# RobotComputerVision_1_1.net
KiCad netlist of a schematic drawn in Altium Designer
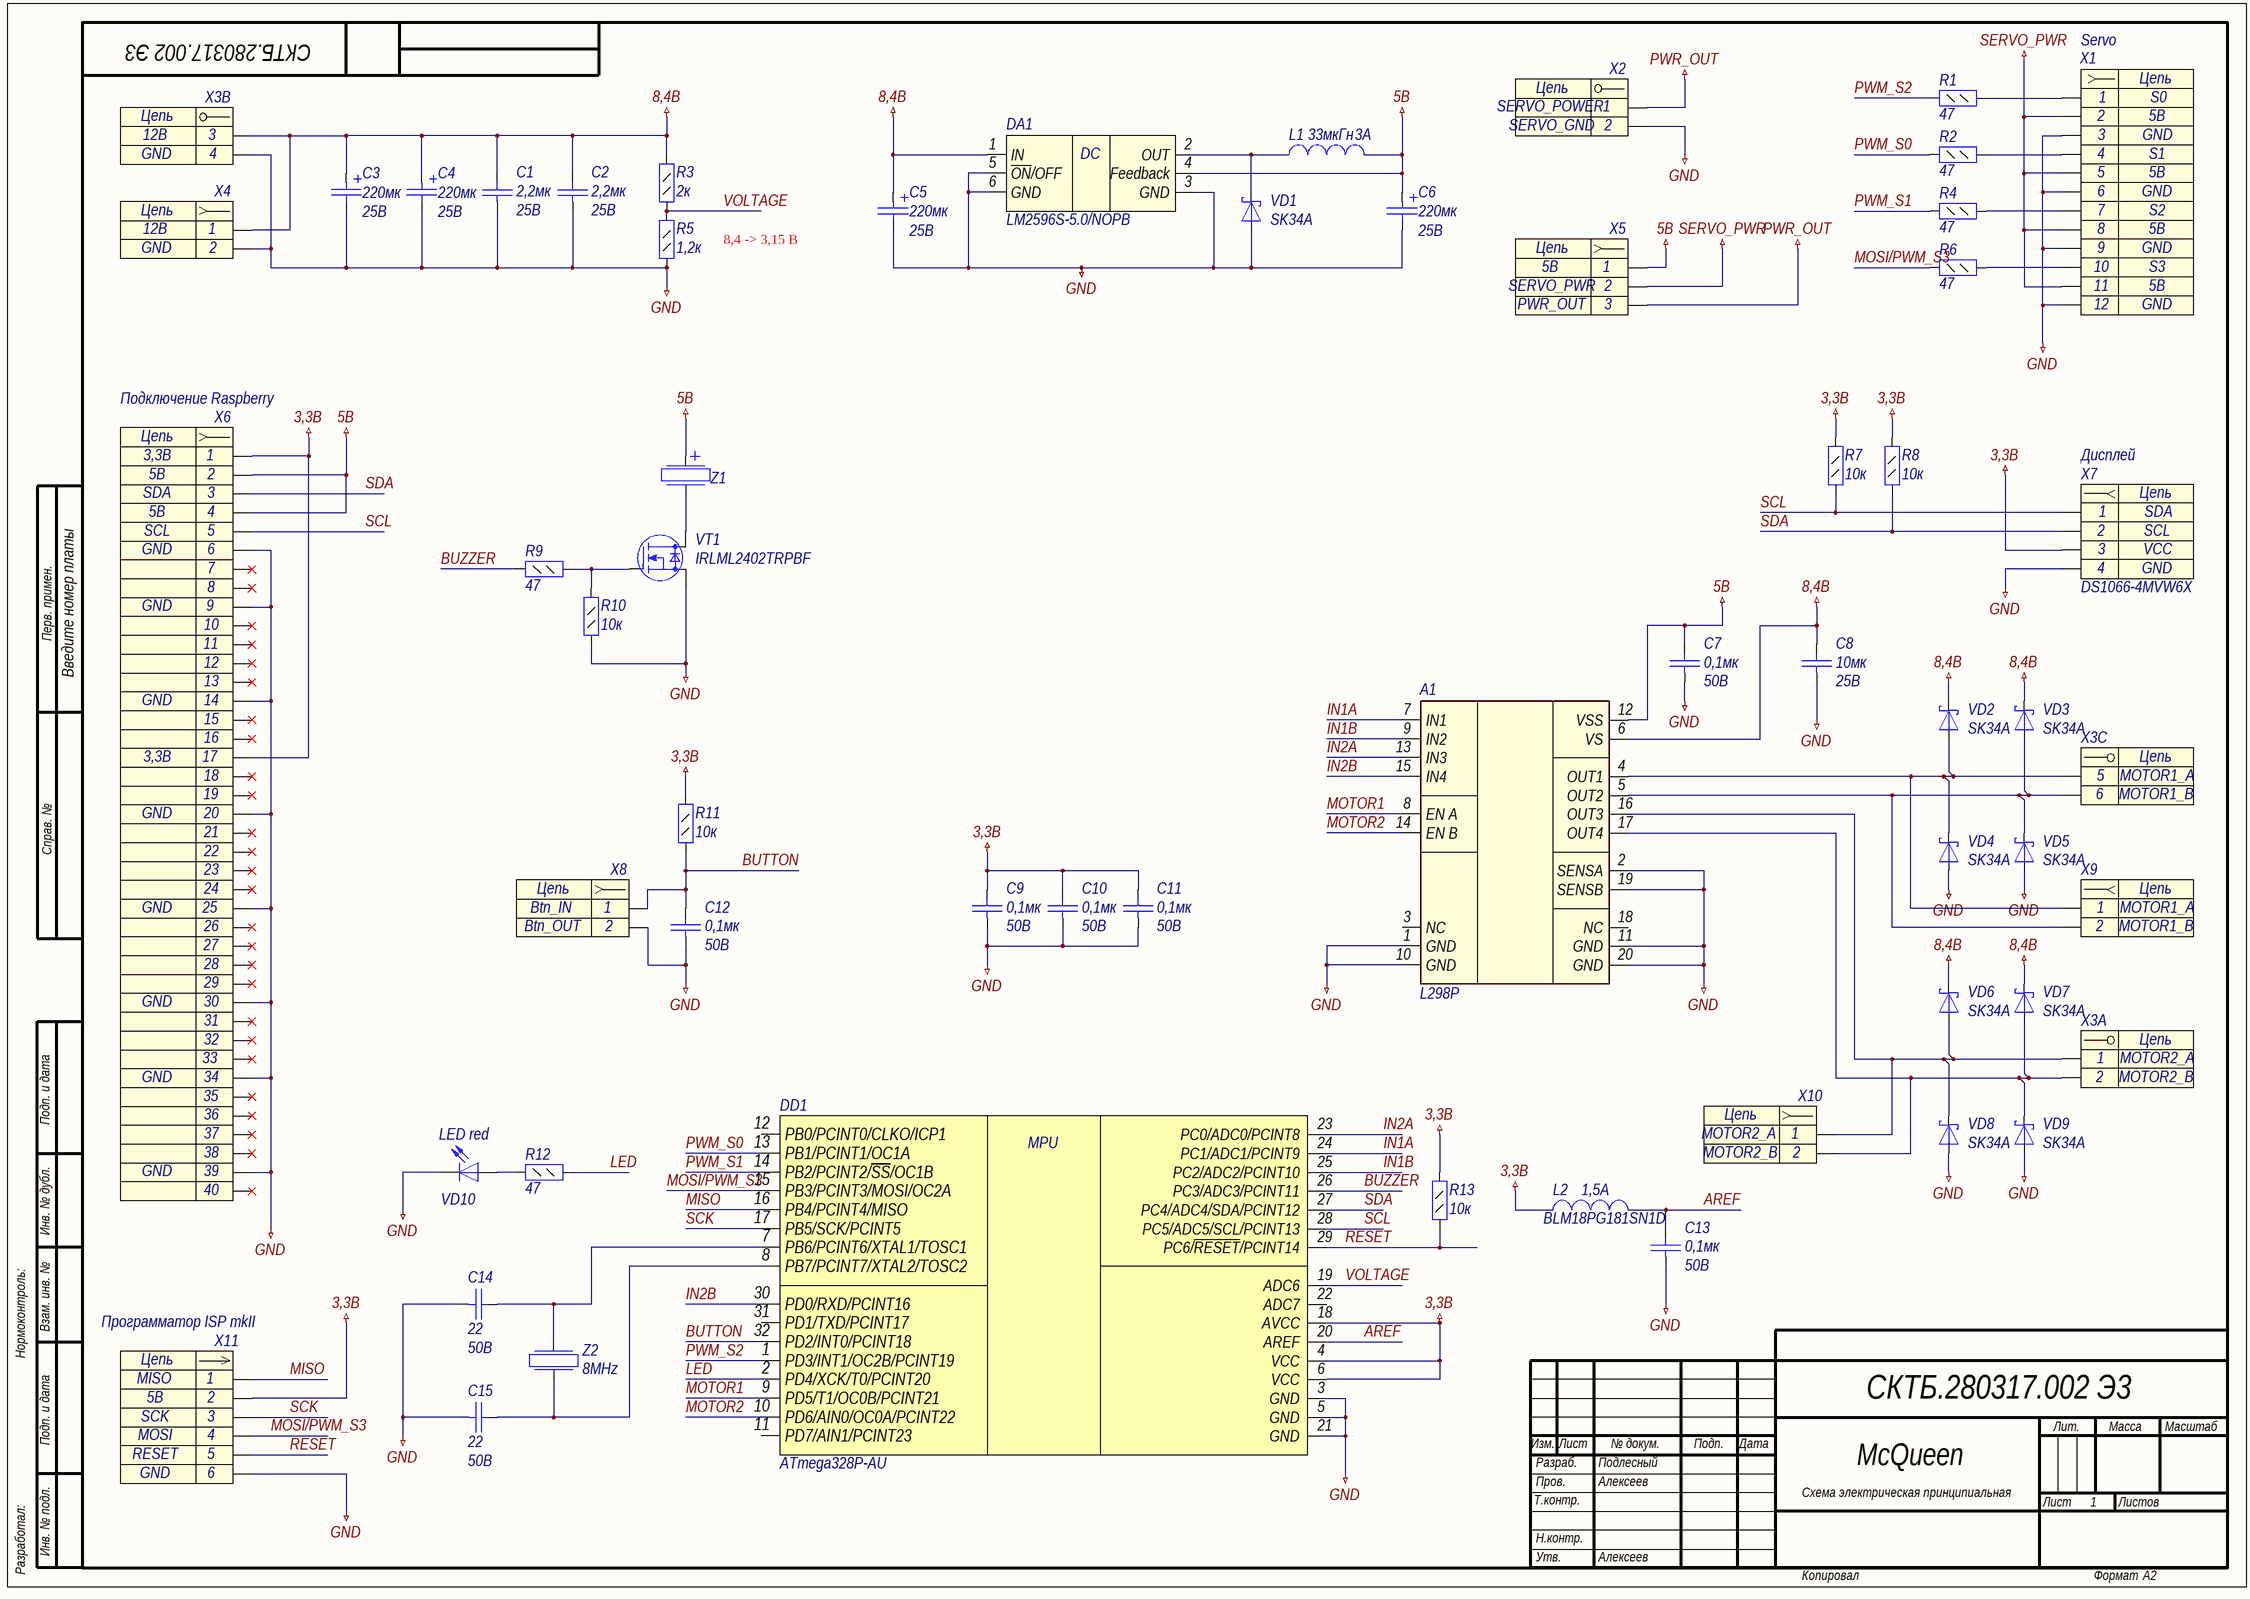
[diagram p0: RobotComputerVision_1.1.SchDoc]

(export (version "E")
  (design (tool "Eeschema 10.0.6"))
  (components
    (comp (ref "A1")
      (value "L298P")
      (footprint "POWERSO20")
      (description "FULL BRIDGE DC MOTOR DRIVER")
      (libsource (lib "MOP44") (part "L298P"))
    )
    (comp (ref "C1")
      (value "2,2мк")
      (footprint "C0805")
      (description "Конденсатор")
      (fields (field (name "VOLTAGE") "25B") (field (name "PART NUMBER") "GRM21BR71E225K"))
      (libsource (lib "MOP44") (part "Capacitor"))
    )
    (comp (ref "C2")
      (value "2,2мк")
      (footprint "C0805")
      (description "Конденсатор")
      (fields (field (name "VOLTAGE") "25B") (field (name "PART NUMBER") "GRM21BR71E225K"))
      (libsource (lib "MOP44") (part "Capacitor"))
    )
    (comp (ref "C3")
      (value "220мк")
      (footprint "Cap_SMD_radial_polar(8x10.2)")
      (description "Конденсатор полярный")
      (fields
        (field (name "VOLTAGE") "25В")
        (field (name "PART NUMBER") "JCK1E221M080105")
        (field (name "Comment") "Capacitor_pol")
      )
      (libsource (lib "MOP44") (part "Capacitor_pol"))
    )
    (comp (ref "C4")
      (value "220мк")
      (footprint "Cap_SMD_radial_polar(8x10.2)")
      (description "Конденсатор полярный")
      (fields
        (field (name "VOLTAGE") "25В")
        (field (name "PART NUMBER") "JCK1E221M080105")
        (field (name "Comment") "Capacitor_pol")
      )
      (libsource (lib "MOP44") (part "Capacitor_pol"))
    )
    (comp (ref "C5")
      (value "220мк")
      (footprint "Cap_SMD_radial_polar(8x10.2)")
      (description "Конденсатор полярный")
      (fields
        (field (name "VOLTAGE") "25В")
        (field (name "PART NUMBER") "JCK1E221M080105")
        (field (name "Comment") "Capacitor_pol")
      )
      (libsource (lib "MOP44") (part "Capacitor_pol"))
    )
    (comp (ref "C6")
      (value "220мк")
      (footprint "Cap_SMD_radial_polar(8x10.2)")
      (description "Конденсатор полярный")
      (fields
        (field (name "VOLTAGE") "25В")
        (field (name "PART NUMBER") "JCK1E221M080105")
        (field (name "Comment") "Capacitor_pol")
      )
      (libsource (lib "MOP44") (part "Capacitor_pol"))
    )
    (comp (ref "C7")
      (value "0,1мк")
      (footprint "C0805")
      (description "Конденсатор")
      (fields (field (name "VOLTAGE") "50В") (field (name "PART NUMBER") "GRM21BR71H104KA01L "))
      (libsource (lib "MOP44") (part "Capacitor"))
    )
    (comp (ref "C8")
      (value "10мк")
      (footprint "C1210")
      (description "Конденсатор")
      (fields (field (name "VOLTAGE") "25В") (field (name "PART NUMBER") "GRM32ER61A106K"))
      (libsource (lib "MOP44") (part "Capacitor"))
    )
    (comp (ref "C9")
      (value "0,1мк")
      (footprint "C0805")
      (description "Конденсатор")
      (fields (field (name "VOLTAGE") "50В") (field (name "PART NUMBER") "GRM21BR71H104KA01L "))
      (libsource (lib "MOP44") (part "Capacitor"))
    )
    (comp (ref "C10")
      (value "0,1мк")
      (footprint "C0805")
      (description "Конденсатор")
      (fields (field (name "VOLTAGE") "50В") (field (name "PART NUMBER") "GRM21BR71H104KA01L "))
      (libsource (lib "MOP44") (part "Capacitor"))
    )
    (comp (ref "C11")
      (value "0,1мк")
      (footprint "C0805")
      (description "Конденсатор")
      (fields (field (name "VOLTAGE") "50В") (field (name "PART NUMBER") "GRM21BR71H104KA01L "))
      (libsource (lib "MOP44") (part "Capacitor"))
    )
    (comp (ref "C12")
      (value "0,1мк")
      (footprint "C0805")
      (description "Конденсатор")
      (fields (field (name "VOLTAGE") "50В") (field (name "PART NUMBER") "GRM21BR71H104KA01L "))
      (libsource (lib "MOP44") (part "Capacitor"))
    )
    (comp (ref "C13")
      (value "0,1мк")
      (footprint "C0805")
      (description "Конденсатор")
      (fields (field (name "VOLTAGE") "50В") (field (name "PART NUMBER") "GRM21BR71H104KA01L "))
      (libsource (lib "MOP44") (part "Capacitor"))
    )
    (comp (ref "C14")
      (value "22")
      (footprint "C0805")
      (description "Конденсатор")
      (fields (field (name "VOLTAGE") "50В") (field (name "PART NUMBER") "MLCC22pFNPO50V5%0805"))
      (libsource (lib "MOP44") (part "Capacitor"))
    )
    (comp (ref "C15")
      (value "22")
      (footprint "C0805")
      (description "Конденсатор")
      (fields (field (name "VOLTAGE") "50В") (field (name "PART NUMBER") "MLCC22pFNPO50V5%0805"))
      (libsource (lib "MOP44") (part "Capacitor"))
    )
    (comp (ref "DA1")
      (value "LM2596S")
      (footprint "TO-263-5")
      (description "3-A Step-Down Voltage Regulator")
      (fields
        (field (name "PART NUMBER") "LM2596S-5.0/NOPB")
        (field (name "MANUFACTURER") "Texas Instruments")
      )
      (libsource (lib "MOP44") (part "LM2596S"))
    )
    (comp (ref "DD1")
      (value "ATmega328P-AU")
      (footprint "TQFP-32")
      (description "Микроконтроллер 8-Бит, picoPower, AVR, 20МГц, 32КБ Flash")
      (libsource (lib "MOP44") (part "ATmega328P-AU"))
    )
    (comp (ref "L1")
      (value "33мкГн")
      (footprint "IND_12.5x12.5")
      (description "EMI Suppression Filter")
      (fields
        (field (name "RATED CURRENT") "3A")
        (field (name "PART NUMBER") "B82477G4333M000")
        (field (name "Comment") "Inductor")
      )
      (libsource (lib "MOP44") (part "Inductor"))
    )
    (comp (ref "L2")
      (value "Inductor")
      (footprint "L0603")
      (description "EMI Suppression Filter")
      (fields (field (name "RATED CURRENT") "1,5A") (field (name "PART NUMBER") "BLM18PG181SN1D"))
      (libsource (lib "MOP44") (part "Inductor"))
    )
    (comp (ref "R1")
      (value "47")
      (footprint "R0805")
      (description "Резистор")
      (fields (field (name "PART NUMBER") "RC0805FR-0747RL") (field (name "POWER") "0,125Вт"))
      (libsource (lib "") (part "Resistor_0,125Вт_1"))
    )
    (comp (ref "R2")
      (value "47")
      (footprint "R0805")
      (description "Резистор")
      (fields (field (name "PART NUMBER") "RC0805FR-0747RL") (field (name "POWER") "0,125Вт"))
      (libsource (lib "") (part "Resistor_0,125Вт_1"))
    )
    (comp (ref "R3")
      (value "2к")
      (footprint "R0805")
      (description "Резистор")
      (fields (field (name "PART NUMBER") "RC0805FR-072KL") (field (name "POWER") "0,125Вт"))
      (libsource (lib "MOP44") (part "Resistor_0,125Вт"))
    )
    (comp (ref "R4")
      (value "47")
      (footprint "R0805")
      (description "Резистор")
      (fields (field (name "PART NUMBER") "RC0805FR-0747RL") (field (name "POWER") "0,125Вт"))
      (libsource (lib "") (part "Resistor_0,125Вт_1"))
    )
    (comp (ref "R5")
      (value "1,2к")
      (footprint "R0805")
      (description "Резистор")
      (fields (field (name "PART NUMBER") "RC0805FR-071K2") (field (name "POWER") "0,125Вт"))
      (libsource (lib "MOP44") (part "Resistor_0,125Вт"))
    )
    (comp (ref "R6")
      (value "47")
      (footprint "R0805")
      (description "Резистор")
      (fields (field (name "PART NUMBER") "RC0805FR-0747RL") (field (name "POWER") "0,125Вт"))
      (libsource (lib "") (part "Resistor_0,125Вт_1"))
    )
    (comp (ref "R7")
      (value "10к")
      (footprint "R0805")
      (description "Резистор")
      (fields (field (name "PART NUMBER") "RC0805FR-0710KL") (field (name "POWER") "0,125Вт"))
      (libsource (lib "MOP44") (part "Resistor_0,125Вт"))
    )
    (comp (ref "R8")
      (value "10к")
      (footprint "R0805")
      (description "Резистор")
      (fields (field (name "PART NUMBER") "RC0805FR-0710KL") (field (name "POWER") "0,125Вт"))
      (libsource (lib "MOP44") (part "Resistor_0,125Вт"))
    )
    (comp (ref "R9")
      (value "47")
      (footprint "R0805")
      (description "Резистор")
      (fields (field (name "PART NUMBER") "RC0805FR-0747RL") (field (name "POWER") "0,125Вт"))
      (libsource (lib "") (part "Resistor_0,125Вт_1"))
    )
    (comp (ref "R10")
      (value "10к")
      (footprint "R0805")
      (description "Резистор")
      (fields (field (name "PART NUMBER") "RC0805FR-0710KL") (field (name "POWER") "0,125Вт"))
      (libsource (lib "MOP44") (part "Resistor_0,125Вт"))
    )
    (comp (ref "R11")
      (value "10к")
      (footprint "R0805")
      (description "Резистор")
      (fields (field (name "PART NUMBER") "RC0805FR-0710KL") (field (name "POWER") "0,125Вт"))
      (libsource (lib "MOP44") (part "Resistor_0,125Вт"))
    )
    (comp (ref "R12")
      (value "47")
      (footprint "R0805")
      (description "Резистор")
      (fields (field (name "PART NUMBER") "RC0805FR-0747RL") (field (name "POWER") "0,125Вт"))
      (libsource (lib "") (part "Resistor_0,125Вт_1"))
    )
    (comp (ref "R13")
      (value "10к")
      (footprint "R0805")
      (description "Резистор")
      (fields (field (name "PART NUMBER") "RC0805FR-0710KL") (field (name "POWER") "0,125Вт"))
      (libsource (lib "MOP44") (part "Resistor_0,125Вт"))
    )
    (comp (ref "VD1")
      (value "DiodeSchottky")
      (footprint "SMA")
      (description "Диод Шоттки")
      (fields (field (name "PART NUMBER") "SK34A"))
      (libsource (lib "MOP44") (part "DiodeSchottky"))
    )
    (comp (ref "VD2")
      (value "DiodeSchottky")
      (footprint "SMA")
      (description "Диод Шоттки")
      (fields (field (name "PART NUMBER") "SK34A"))
      (libsource (lib "MOP44") (part "DiodeSchottky"))
    )
    (comp (ref "VD3")
      (value "DiodeSchottky")
      (footprint "SMA")
      (description "Диод Шоттки")
      (fields (field (name "PART NUMBER") "SK34A"))
      (libsource (lib "MOP44") (part "DiodeSchottky"))
    )
    (comp (ref "VD4")
      (value "DiodeSchottky")
      (footprint "SMA")
      (description "Диод Шоттки")
      (fields (field (name "PART NUMBER") "SK34A"))
      (libsource (lib "MOP44") (part "DiodeSchottky"))
    )
    (comp (ref "VD5")
      (value "DiodeSchottky")
      (footprint "SMA")
      (description "Диод Шоттки")
      (fields (field (name "PART NUMBER") "SK34A"))
      (libsource (lib "MOP44") (part "DiodeSchottky"))
    )
    (comp (ref "VD6")
      (value "DiodeSchottky")
      (footprint "SMA")
      (description "Диод Шоттки")
      (fields (field (name "PART NUMBER") "SK34A"))
      (libsource (lib "MOP44") (part "DiodeSchottky"))
    )
    (comp (ref "VD7")
      (value "DiodeSchottky")
      (footprint "SMA")
      (description "Диод Шоттки")
      (fields (field (name "PART NUMBER") "SK34A"))
      (libsource (lib "MOP44") (part "DiodeSchottky"))
    )
    (comp (ref "VD8")
      (value "DiodeSchottky")
      (footprint "SMA")
      (description "Диод Шоттки")
      (fields (field (name "PART NUMBER") "SK34A"))
      (libsource (lib "MOP44") (part "DiodeSchottky"))
    )
    (comp (ref "VD9")
      (value "DiodeSchottky")
      (footprint "SMA")
      (description "Диод Шоттки")
      (fields (field (name "PART NUMBER") "SK34A"))
      (libsource (lib "MOP44") (part "DiodeSchottky"))
    )
    (comp (ref "VD10")
      (value "LED")
      (footprint "L_0805")
      (description "Светодиод")
      (fields (field (name "PART NAME") "LED red") (field (name "PART NUMBER") "KP-2012EC"))
      (libsource (lib "MOP44") (part "LED"))
    )
    (comp (ref "VT1")
      (value "N-MOSFET")
      (footprint "SOT23-3")
      (fields
        (field (name "PART NUMBER") "IRLML2402TRPBF")
        (field (name "MANUFACTURER") "International Rectifier")
      )
      (libsource (lib "MOP44") (part "N-MOSFET"))
    )
    (comp (ref "X1")
      (value "Servo")
      (footprint "PLS-12")
      (description "Разъем - 12 конт. розетка")
      (libsource (lib "MOP44") (part "Header_12_sct"))
    )
    (comp (ref "X2")
      (value "Header_2_trm")
      (footprint "TERMINAL-2WAY-3.5MM")
      (description "Разъем - 2 конт. клеммник")
      (libsource (lib "MOP44") (part "Header_2_trm"))
    )
    (comp (ref "X3")
      (value "~")
      (footprint "TERMINAL-6WAY-5MM")
      (description "POWER")
      (libsource (lib "MOP44") (part "Header_6_motor"))
    )
    (comp (ref "X4")
      (value "Header_2_sct")
      (footprint "2HOLE_2.5")
      (description "Разъем - 2 конт. розетка")
      (libsource (lib "MOP44") (part "Header_2_sct"))
    )
    (comp (ref "X5")
      (value "Header_3_sct")
      (footprint "TAB_3PAD")
      (description "Разъем - 3 конт. розетка")
      (libsource (lib "MOP44") (part "Header_3_sct"))
    )
    (comp (ref "X6")
      (value "Подключение Raspberry")
      (footprint "PBS-40")
      (description "Разъем - 5 конт. розетка")
      (libsource (lib "MOP44") (part "Header_40_sct"))
    )
    (comp (ref "X7")
      (value "Дисплей")
      (footprint "MW-4M")
      (description "Разъем - 4 конт. розетка")
      (fields (field (name "PART NUMBER") "DS1066-4MVW6X"))
      (libsource (lib "MOP44") (part "Header_4_sct"))
    )
    (comp (ref "X8")
      (value "Header_2_sct")
      (footprint "2HOLE_2.5")
      (description "Разъем - 2 конт. розетка")
      (libsource (lib "MOP44") (part "Header_2_sct"))
    )
    (comp (ref "X9")
      (value "Header_2_sct")
      (footprint "2HOLE_2.5")
      (description "Разъем - 2 конт. розетка")
      (libsource (lib "") (part "Header_2_sct_1"))
    )
    (comp (ref "X10")
      (value "Header_2_sct")
      (footprint "2HOLE_2.5")
      (description "Разъем - 2 конт. розетка")
      (libsource (lib "MOP44") (part "Header_2_sct"))
    )
    (comp (ref "X11")
      (value "Программатор ISP mkII")
      (footprint "PLS2-6")
      (description "Разъем - 6 конт. вилка")
      (libsource (lib "MOP44") (part "ISP MKII"))
    )
    (comp (ref "Z1")
      (value "~")
      (footprint "Buzzer_gen_12mm")
      (description "Пьезоизлучатель звуковой без генератора")
      (fields (field (name "PART NUMBER") "HCM1212X"))
      (libsource (lib "MOP44") (part "Buzzer"))
    )
    (comp (ref "Z2")
      (value "Crystal")
      (footprint "QSMD5.0x3.2x1.0")
      (description "Кварцевый резонатор")
      (fields (field (name "FREQUENCE") "8MHz") (field (name "PART NUMBER") "KX-9A"))
      (libsource (lib "MOP44") (part "Crystal"))
    )
  )
  (nets
    (net (code "1") (name "/AREF") (class "Default")
      (node (ref "C13") (pin "2") (pinfunction "2_2") (pintype "passive"))
      (node (ref "DD1") (pin "20") (pinfunction "AREF_20") (pintype "passive"))
      (node (ref "L2") (pin "2") (pinfunction "2_2") (pintype "passive"))
    )
    (net (code "2") (name "/BUTTON") (class "Default")
      (node (ref "C12") (pin "2") (pinfunction "2_2") (pintype "passive"))
      (node (ref "DD1") (pin "32") (pinfunction "PD2/INT0/PCINT18_32") (pintype "passive"))
      (node (ref "R11") (pin "1") (pinfunction "1_1") (pintype "passive"))
      (node (ref "X8") (pin "1") (pinfunction "1_1") (pintype "passive"))
    )
    (net (code "3") (name "/BUZZER") (class "Default")
      (node (ref "DD1") (pin "26") (pinfunction "PC3/ADC3/PCINT11_26") (pintype "passive"))
      (node (ref "R9") (pin "1") (pinfunction "1_1") (pintype "passive"))
    )
    (net (code "4") (name "/IN1A") (class "Default")
      (node (ref "A1") (pin "7") (pinfunction "IN1_7") (pintype "passive"))
      (node (ref "DD1") (pin "24") (pinfunction "PC1/ADC1/PCINT9_24") (pintype "passive"))
    )
    (net (code "5") (name "/IN1B") (class "Default")
      (node (ref "A1") (pin "9") (pinfunction "IN2_9") (pintype "passive"))
      (node (ref "DD1") (pin "25") (pinfunction "PC2/ADC2/PCINT10_25") (pintype "passive"))
    )
    (net (code "6") (name "/IN2A") (class "Default")
      (node (ref "A1") (pin "13") (pinfunction "IN3_13") (pintype "passive"))
      (node (ref "DD1") (pin "23") (pinfunction "PC0/ADC0/PCINT8_23") (pintype "passive"))
    )
    (net (code "7") (name "/IN2B") (class "Default")
      (node (ref "A1") (pin "15") (pinfunction "IN4_15") (pintype "passive"))
      (node (ref "DD1") (pin "30") (pinfunction "PD0/RXD/PCINT16_30") (pintype "passive"))
    )
    (net (code "8") (name "/LED") (class "Default")
      (node (ref "DD1") (pin "2") (pinfunction "PD4/XCK/T0/PCINT20_2") (pintype "passive"))
      (node (ref "R12") (pin "2") (pinfunction "2_2") (pintype "passive"))
    )
    (net (code "9") (name "/MISO") (class "Default")
      (node (ref "DD1") (pin "16") (pinfunction "PB4/PCINT4/MISO_16") (pintype "passive"))
      (node (ref "X11") (pin "1") (pinfunction "1_1") (pintype "passive"))
    )
    (net (code "10") (name "/MOSI{slash}PWM_S3") (class "Default")
      (node (ref "DD1") (pin "15") (pinfunction "PB3/PCINT3/MOSI/OC2A_15") (pintype "passive"))
      (node (ref "R6") (pin "1") (pinfunction "1_1") (pintype "passive"))
      (node (ref "X11") (pin "4") (pinfunction "4_4") (pintype "passive"))
    )
    (net (code "11") (name "/MOTOR1") (class "Default")
      (node (ref "A1") (pin "8") (pinfunction "EN_A_8") (pintype "passive"))
      (node (ref "DD1") (pin "9") (pinfunction "PD5/T1/OC0B/PCINT21_9") (pintype "passive"))
    )
    (net (code "12") (name "/MOTOR2") (class "Default")
      (node (ref "A1") (pin "14") (pinfunction "EN_B_14") (pintype "passive"))
      (node (ref "DD1") (pin "10") (pinfunction "PD6/AIN0/OC0A/PCINT22_10") (pintype "passive"))
    )
    (net (code "13") (name "/PWM_S0") (class "Default")
      (node (ref "DD1") (pin "13") (pinfunction "PB1/PCINT1/OC1A_13") (pintype "passive"))
      (node (ref "R2") (pin "1") (pinfunction "1_1") (pintype "passive"))
    )
    (net (code "14") (name "/PWM_S1") (class "Default")
      (node (ref "DD1") (pin "14") (pinfunction "PB2/PCINT2/~{SS}/OC1B_14") (pintype "passive"))
      (node (ref "R4") (pin "1") (pinfunction "1_1") (pintype "passive"))
    )
    (net (code "15") (name "/PWM_S2") (class "Default")
      (node (ref "DD1") (pin "1") (pinfunction "PD3/INT1/OC2B/PCINT19_1") (pintype "passive"))
      (node (ref "R1") (pin "1") (pinfunction "1_1") (pintype "passive"))
    )
    (net (code "16") (name "/RESET") (class "Default")
      (node (ref "DD1") (pin "29") (pinfunction "PC6/~{RESET}/PCINT14_29") (pintype "passive"))
      (node (ref "R13") (pin "1") (pinfunction "1_1") (pintype "passive"))
      (node (ref "X11") (pin "5") (pinfunction "5_5") (pintype "passive"))
    )
    (net (code "17") (name "/SCK") (class "Default")
      (node (ref "DD1") (pin "17") (pinfunction "PB5/SCK/PCINT5_17") (pintype "passive"))
      (node (ref "X11") (pin "3") (pinfunction "3_3") (pintype "passive"))
    )
    (net (code "18") (name "/SCL") (class "Default")
      (node (ref "DD1") (pin "28") (pinfunction "PC5/ADC5/SCL/PCINT13_28") (pintype "passive"))
      (node (ref "R7") (pin "1") (pinfunction "1_1") (pintype "passive"))
      (node (ref "X6") (pin "5") (pinfunction "5_5") (pintype "passive"))
      (node (ref "X7") (pin "1") (pinfunction "1_1") (pintype "passive"))
    )
    (net (code "19") (name "/SDA") (class "Default")
      (node (ref "DD1") (pin "27") (pinfunction "PC4/ADC4/SDA/PCINT12_27") (pintype "passive"))
      (node (ref "R8") (pin "1") (pinfunction "1_1") (pintype "passive"))
      (node (ref "X6") (pin "3") (pinfunction "3_3") (pintype "passive"))
      (node (ref "X7") (pin "2") (pinfunction "2_2") (pintype "passive"))
    )
    (net (code "20") (name "/VOLTAGE") (class "Default")
      (node (ref "DD1") (pin "19") (pinfunction "ADC6_19") (pintype "passive"))
      (node (ref "R3") (pin "1") (pinfunction "1_1") (pintype "passive"))
      (node (ref "R5") (pin "2") (pinfunction "2_2") (pintype "passive"))
    )
    (net (code "21") (name "3,3B") (class "Default")
      (node (ref "C10") (pin "2") (pinfunction "2_2") (pintype "passive"))
      (node (ref "C11") (pin "2") (pinfunction "2_2") (pintype "passive"))
      (node (ref "C9") (pin "2") (pinfunction "2_2") (pintype "passive"))
      (node (ref "DD1") (pin "18") (pinfunction "AVCC_18") (pintype "passive"))
      (node (ref "DD1") (pin "4") (pinfunction "VCC_4") (pintype "passive"))
      (node (ref "DD1") (pin "6") (pinfunction "VCC_6") (pintype "passive"))
      (node (ref "L2") (pin "1") (pinfunction "1_1") (pintype "passive"))
      (node (ref "R11") (pin "2") (pinfunction "2_2") (pintype "passive"))
      (node (ref "R13") (pin "2") (pinfunction "2_2") (pintype "passive"))
      (node (ref "R7") (pin "2") (pinfunction "2_2") (pintype "passive"))
      (node (ref "R8") (pin "2") (pinfunction "2_2") (pintype "passive"))
      (node (ref "X11") (pin "2") (pinfunction "2_2") (pintype "passive"))
      (node (ref "X6") (pin "1") (pinfunction "1_1") (pintype "passive"))
      (node (ref "X6") (pin "17") (pinfunction "17_17") (pintype "passive"))
      (node (ref "X7") (pin "3") (pinfunction "3_3") (pintype "passive"))
    )
    (net (code "22") (name "5В") (class "Default")
      (node (ref "A1") (pin "12") (pinfunction "VSS_12") (pintype "passive"))
      (node (ref "C6") (pin "1") (pinfunction "1_1") (pintype "passive"))
      (node (ref "C7") (pin "2") (pinfunction "2_2") (pintype "passive"))
      (node (ref "DA1") (pin "4") (pinfunction "Feedback_4") (pintype "power_in"))
      (node (ref "L1") (pin "2") (pinfunction "2_2") (pintype "passive"))
      (node (ref "X5") (pin "1") (pinfunction "1_1") (pintype "passive"))
      (node (ref "X6") (pin "2") (pinfunction "2_2") (pintype "passive"))
      (node (ref "X6") (pin "4") (pinfunction "4_4") (pintype "passive"))
      (node (ref "Z1") (pin "1") (pinfunction "1_1") (pintype "passive"))
    )
    (net (code "23") (name "8,4В") (class "Default")
      (node (ref "A1") (pin "6") (pinfunction "VS_6") (pintype "passive"))
      (node (ref "C1") (pin "2") (pinfunction "2_2") (pintype "passive"))
      (node (ref "C2") (pin "2") (pinfunction "2_2") (pintype "passive"))
      (node (ref "C3") (pin "1") (pinfunction "1_1") (pintype "passive"))
      (node (ref "C4") (pin "1") (pinfunction "1_1") (pintype "passive"))
      (node (ref "C5") (pin "1") (pinfunction "1_1") (pintype "passive"))
      (node (ref "C8") (pin "2") (pinfunction "2_2") (pintype "passive"))
      (node (ref "DA1") (pin "1") (pinfunction "IN_1") (pintype "power_in"))
      (node (ref "R3") (pin "2") (pinfunction "2_2") (pintype "passive"))
      (node (ref "VD2") (pin "1") (pinfunction "K_1") (pintype "passive"))
      (node (ref "VD3") (pin "1") (pinfunction "K_1") (pintype "passive"))
      (node (ref "VD6") (pin "1") (pinfunction "K_1") (pintype "passive"))
      (node (ref "VD7") (pin "1") (pinfunction "K_1") (pintype "passive"))
      (node (ref "X3") (pin "3") (pinfunction "3_3") (pintype "passive"))
      (node (ref "X4") (pin "1") (pinfunction "1_1") (pintype "passive"))
    )
    (net (code "24") (name "GND") (class "Default")
      (node (ref "A1") (pin "1") (pinfunction "GND_1") (pintype "passive"))
      (node (ref "A1") (pin "10") (pinfunction "GND_10") (pintype "passive"))
      (node (ref "A1") (pin "11") (pinfunction "GND_11") (pintype "passive"))
      (node (ref "A1") (pin "19") (pinfunction "SENSB_19") (pintype "passive"))
      (node (ref "A1") (pin "2") (pinfunction "SENSA_2") (pintype "passive"))
      (node (ref "A1") (pin "20") (pinfunction "GND_20") (pintype "passive"))
      (node (ref "C1") (pin "1") (pinfunction "1_1") (pintype "passive"))
      (node (ref "C10") (pin "1") (pinfunction "1_1") (pintype "passive"))
      (node (ref "C11") (pin "1") (pinfunction "1_1") (pintype "passive"))
      (node (ref "C12") (pin "1") (pinfunction "1_1") (pintype "passive"))
      (node (ref "C13") (pin "1") (pinfunction "1_1") (pintype "passive"))
      (node (ref "C14") (pin "1") (pinfunction "1_1") (pintype "passive"))
      (node (ref "C15") (pin "1") (pinfunction "1_1") (pintype "passive"))
      (node (ref "C2") (pin "1") (pinfunction "1_1") (pintype "passive"))
      (node (ref "C3") (pin "2") (pinfunction "2_2") (pintype "passive"))
      (node (ref "C4") (pin "2") (pinfunction "2_2") (pintype "passive"))
      (node (ref "C5") (pin "2") (pinfunction "2_2") (pintype "passive"))
      (node (ref "C6") (pin "2") (pinfunction "2_2") (pintype "passive"))
      (node (ref "C7") (pin "1") (pinfunction "1_1") (pintype "passive"))
      (node (ref "C8") (pin "1") (pinfunction "1_1") (pintype "passive"))
      (node (ref "C9") (pin "1") (pinfunction "1_1") (pintype "passive"))
      (node (ref "DA1") (pin "3") (pinfunction "GND_3") (pintype "power_in"))
      (node (ref "DA1") (pin "5") (pinfunction "~{ON}/OFF_5") (pintype "power_in"))
      (node (ref "DA1") (pin "6") (pinfunction "GND_6") (pintype "power_in"))
      (node (ref "DD1") (pin "21") (pinfunction "GND_21") (pintype "passive"))
      (node (ref "DD1") (pin "3") (pinfunction "GND_3") (pintype "passive"))
      (node (ref "DD1") (pin "5") (pinfunction "GND_5") (pintype "passive"))
      (node (ref "R10") (pin "1") (pinfunction "1_1") (pintype "passive"))
      (node (ref "R5") (pin "1") (pinfunction "1_1") (pintype "passive"))
      (node (ref "VD1") (pin "2") (pinfunction "A_2") (pintype "passive"))
      (node (ref "VD10") (pin "1") (pinfunction "K_1") (pintype "passive"))
      (node (ref "VD4") (pin "2") (pinfunction "A_2") (pintype "passive"))
      (node (ref "VD5") (pin "2") (pinfunction "A_2") (pintype "passive"))
      (node (ref "VD8") (pin "2") (pinfunction "A_2") (pintype "passive"))
      (node (ref "VD9") (pin "2") (pinfunction "A_2") (pintype "passive"))
      (node (ref "VT1") (pin "3") (pinfunction "S_3") (pintype "passive"))
      (node (ref "X1") (pin "12") (pinfunction "12_12") (pintype "passive"))
      (node (ref "X1") (pin "3") (pinfunction "3_3") (pintype "passive"))
      (node (ref "X1") (pin "6") (pinfunction "6_6") (pintype "passive"))
      (node (ref "X1") (pin "9") (pinfunction "9_9") (pintype "passive"))
      (node (ref "X11") (pin "6") (pinfunction "6_6") (pintype "passive"))
      (node (ref "X2") (pin "2") (pinfunction "2_2") (pintype "passive"))
      (node (ref "X3") (pin "4") (pinfunction "4_4") (pintype "passive"))
      (node (ref "X4") (pin "2") (pinfunction "2_2") (pintype "passive"))
      (node (ref "X6") (pin "14") (pinfunction "14_14") (pintype "passive"))
      (node (ref "X6") (pin "20") (pinfunction "20_20") (pintype "passive"))
      (node (ref "X6") (pin "25") (pinfunction "25_25") (pintype "passive"))
      (node (ref "X6") (pin "30") (pinfunction "30_30") (pintype "passive"))
      (node (ref "X6") (pin "34") (pinfunction "34_34") (pintype "passive"))
      (node (ref "X6") (pin "39") (pinfunction "39_39") (pintype "passive"))
      (node (ref "X6") (pin "6") (pinfunction "6_6") (pintype "passive"))
      (node (ref "X6") (pin "9") (pinfunction "9_9") (pintype "passive"))
      (node (ref "X7") (pin "4") (pinfunction "4_4") (pintype "passive"))
      (node (ref "X8") (pin "2") (pinfunction "2_2") (pintype "passive"))
    )
    (net (code "25") (name "Net-(A1-OUT1)") (class "Default")
      (node (ref "A1") (pin "4") (pinfunction "OUT1_4") (pintype "passive"))
      (node (ref "VD2") (pin "2") (pinfunction "A_2") (pintype "passive"))
      (node (ref "VD4") (pin "1") (pinfunction "K_1") (pintype "passive"))
      (node (ref "X3") (pin "5") (pinfunction "5_5") (pintype "passive"))
      (node (ref "X9") (pin "1") (pinfunction "1_1") (pintype "passive"))
    )
    (net (code "26") (name "Net-(A1-OUT2)") (class "Default")
      (node (ref "A1") (pin "5") (pinfunction "OUT2_5") (pintype "passive"))
      (node (ref "VD3") (pin "2") (pinfunction "A_2") (pintype "passive"))
      (node (ref "VD5") (pin "1") (pinfunction "K_1") (pintype "passive"))
      (node (ref "X3") (pin "6") (pinfunction "6_6") (pintype "passive"))
      (node (ref "X9") (pin "2") (pinfunction "2_2") (pintype "passive"))
    )
    (net (code "27") (name "Net-(A1-OUT3)") (class "Default")
      (node (ref "A1") (pin "16") (pinfunction "OUT3_16") (pintype "passive"))
      (node (ref "VD6") (pin "2") (pinfunction "A_2") (pintype "passive"))
      (node (ref "VD8") (pin "1") (pinfunction "K_1") (pintype "passive"))
      (node (ref "X10") (pin "1") (pinfunction "1_1") (pintype "passive"))
      (node (ref "X3") (pin "1") (pinfunction "1_1") (pintype "passive"))
    )
    (net (code "28") (name "Net-(A1-OUT4)") (class "Default")
      (node (ref "A1") (pin "17") (pinfunction "OUT4_17") (pintype "passive"))
      (node (ref "VD7") (pin "2") (pinfunction "A_2") (pintype "passive"))
      (node (ref "VD9") (pin "1") (pinfunction "K_1") (pintype "passive"))
      (node (ref "X10") (pin "2") (pinfunction "2_2") (pintype "passive"))
      (node (ref "X3") (pin "2") (pinfunction "2_2") (pintype "passive"))
    )
    (net (code "29") (name "Net-(DA1-OUT)") (class "Default")
      (node (ref "DA1") (pin "2") (pinfunction "OUT_2") (pintype "power_in"))
      (node (ref "L1") (pin "1") (pinfunction "1_1") (pintype "passive"))
      (node (ref "VD1") (pin "1") (pinfunction "K_1") (pintype "passive"))
    )
    (net (code "30") (name "Net-(DD1-PB6{slash}PCINT6{slash}XTAL1{slash}TOSC1)") (class "Default")
      (node (ref "C14") (pin "2") (pinfunction "2_2") (pintype "passive"))
      (node (ref "DD1") (pin "7") (pinfunction "PB6/PCINT6/XTAL1/TOSC1_7") (pintype "passive"))
      (node (ref "Z2") (pin "2") (pinfunction "2_2") (pintype "passive"))
    )
    (net (code "31") (name "Net-(DD1-PB7{slash}PCINT7{slash}XTAL2{slash}TOSC2)") (class "Default")
      (node (ref "C15") (pin "2") (pinfunction "2_2") (pintype "passive"))
      (node (ref "DD1") (pin "8") (pinfunction "PB7/PCINT7/XTAL2/TOSC2_8") (pintype "passive"))
      (node (ref "Z2") (pin "1") (pinfunction "1_1") (pintype "passive"))
    )
    (net (code "32") (name "Net-(R1-Pad2)") (class "Default")
      (node (ref "R1") (pin "2") (pinfunction "2_2") (pintype "passive"))
      (node (ref "X1") (pin "1") (pinfunction "1_1") (pintype "passive"))
    )
    (net (code "33") (name "Net-(R2-Pad2)") (class "Default")
      (node (ref "R2") (pin "2") (pinfunction "2_2") (pintype "passive"))
      (node (ref "X1") (pin "4") (pinfunction "4_4") (pintype "passive"))
    )
    (net (code "34") (name "Net-(R4-Pad2)") (class "Default")
      (node (ref "R4") (pin "2") (pinfunction "2_2") (pintype "passive"))
      (node (ref "X1") (pin "7") (pinfunction "7_7") (pintype "passive"))
    )
    (net (code "35") (name "Net-(R6-Pad2)") (class "Default")
      (node (ref "R6") (pin "2") (pinfunction "2_2") (pintype "passive"))
      (node (ref "X1") (pin "10") (pinfunction "10_10") (pintype "passive"))
    )
    (net (code "36") (name "Net-(VD10-A)") (class "Default")
      (node (ref "R12") (pin "1") (pinfunction "1_1") (pintype "passive"))
      (node (ref "VD10") (pin "2") (pinfunction "A_2") (pintype "passive"))
    )
    (net (code "37") (name "Net-(VT1-D)") (class "Default")
      (node (ref "VT1") (pin "2") (pinfunction "D_2") (pintype "passive"))
      (node (ref "Z1") (pin "2") (pinfunction "2_2") (pintype "passive"))
    )
    (net (code "38") (name "Net-(VT1-G)") (class "Default")
      (node (ref "R10") (pin "2") (pinfunction "2_2") (pintype "passive"))
      (node (ref "R9") (pin "2") (pinfunction "2_2") (pintype "passive"))
      (node (ref "VT1") (pin "1") (pinfunction "G_1") (pintype "passive"))
    )
    (net (code "39") (name "PWR_OUT") (class "Default")
      (node (ref "X2") (pin "1") (pinfunction "1_1") (pintype "passive"))
      (node (ref "X5") (pin "3") (pinfunction "3_3") (pintype "passive"))
    )
    (net (code "40") (name "SERVO_PWR") (class "Default")
      (node (ref "X1") (pin "11") (pinfunction "11_11") (pintype "passive"))
      (node (ref "X1") (pin "2") (pinfunction "2_2") (pintype "passive"))
      (node (ref "X1") (pin "5") (pinfunction "5_5") (pintype "passive"))
      (node (ref "X1") (pin "8") (pinfunction "8_8") (pintype "passive"))
      (node (ref "X5") (pin "2") (pinfunction "2_2") (pintype "passive"))
    )
    (net (code "41") (name "unconnected-(A1-NC-Pad3)") (class "Default")
      (node (ref "A1") (pin "3") (pinfunction "NC_3") (pintype "passive"))
    )
    (net (code "42") (name "unconnected-(A1-NC-Pad18)") (class "Default")
      (node (ref "A1") (pin "18") (pinfunction "NC_18") (pintype "passive"))
    )
    (net (code "43") (name "unconnected-(DD1-ADC7-Pad22)") (class "Default")
      (node (ref "DD1") (pin "22") (pinfunction "ADC7_22") (pintype "passive"))
    )
    (net (code "44") (name "unconnected-(DD1-PB0{slash}PCINT0{slash}CLKO{slash}ICP1-Pad12)") (class "Default")
      (node (ref "DD1") (pin "12") (pinfunction "PB0/PCINT0/CLKO/ICP1_12") (pintype "passive"))
    )
    (net (code "45") (name "unconnected-(DD1-PD1{slash}TXD{slash}PCINT17-Pad31)") (class "Default")
      (node (ref "DD1") (pin "31") (pinfunction "PD1/TXD/PCINT17_31") (pintype "passive"))
    )
    (net (code "46") (name "unconnected-(DD1-PD7{slash}AIN1{slash}PCINT23-Pad11)") (class "Default")
      (node (ref "DD1") (pin "11") (pinfunction "PD7/AIN1/PCINT23_11") (pintype "passive"))
    )
    (net (code "47") (name "unconnected-(X6-Pad7)") (class "Default")
      (node (ref "X6") (pin "7") (pinfunction "7_7") (pintype "passive+no_connect"))
    )
    (net (code "48") (name "unconnected-(X6-Pad8)") (class "Default")
      (node (ref "X6") (pin "8") (pinfunction "8_8") (pintype "passive+no_connect"))
    )
    (net (code "49") (name "unconnected-(X6-Pad10)") (class "Default")
      (node (ref "X6") (pin "10") (pinfunction "10_10") (pintype "passive+no_connect"))
    )
    (net (code "50") (name "unconnected-(X6-Pad11)") (class "Default")
      (node (ref "X6") (pin "11") (pinfunction "11_11") (pintype "passive+no_connect"))
    )
    (net (code "51") (name "unconnected-(X6-Pad12)") (class "Default")
      (node (ref "X6") (pin "12") (pinfunction "12_12") (pintype "passive+no_connect"))
    )
    (net (code "52") (name "unconnected-(X6-Pad13)") (class "Default")
      (node (ref "X6") (pin "13") (pinfunction "13_13") (pintype "passive+no_connect"))
    )
    (net (code "53") (name "unconnected-(X6-Pad15)") (class "Default")
      (node (ref "X6") (pin "15") (pinfunction "15_15") (pintype "passive+no_connect"))
    )
    (net (code "54") (name "unconnected-(X6-Pad16)") (class "Default")
      (node (ref "X6") (pin "16") (pinfunction "16_16") (pintype "passive+no_connect"))
    )
    (net (code "55") (name "unconnected-(X6-Pad18)") (class "Default")
      (node (ref "X6") (pin "18") (pinfunction "18_18") (pintype "passive+no_connect"))
    )
    (net (code "56") (name "unconnected-(X6-Pad19)") (class "Default")
      (node (ref "X6") (pin "19") (pinfunction "19_19") (pintype "passive+no_connect"))
    )
    (net (code "57") (name "unconnected-(X6-Pad21)") (class "Default")
      (node (ref "X6") (pin "21") (pinfunction "21_21") (pintype "passive+no_connect"))
    )
    (net (code "58") (name "unconnected-(X6-Pad22)") (class "Default")
      (node (ref "X6") (pin "22") (pinfunction "22_22") (pintype "passive+no_connect"))
    )
    (net (code "59") (name "unconnected-(X6-Pad23)") (class "Default")
      (node (ref "X6") (pin "23") (pinfunction "23_23") (pintype "passive+no_connect"))
    )
    (net (code "60") (name "unconnected-(X6-Pad24)") (class "Default")
      (node (ref "X6") (pin "24") (pinfunction "24_24") (pintype "passive+no_connect"))
    )
    (net (code "61") (name "unconnected-(X6-Pad26)") (class "Default")
      (node (ref "X6") (pin "26") (pinfunction "26_26") (pintype "passive+no_connect"))
    )
    (net (code "62") (name "unconnected-(X6-Pad27)") (class "Default")
      (node (ref "X6") (pin "27") (pinfunction "27_27") (pintype "passive+no_connect"))
    )
    (net (code "63") (name "unconnected-(X6-Pad28)") (class "Default")
      (node (ref "X6") (pin "28") (pinfunction "28_28") (pintype "passive+no_connect"))
    )
    (net (code "64") (name "unconnected-(X6-Pad29)") (class "Default")
      (node (ref "X6") (pin "29") (pinfunction "29_29") (pintype "passive+no_connect"))
    )
    (net (code "65") (name "unconnected-(X6-Pad31)") (class "Default")
      (node (ref "X6") (pin "31") (pinfunction "31_31") (pintype "passive+no_connect"))
    )
    (net (code "66") (name "unconnected-(X6-Pad32)") (class "Default")
      (node (ref "X6") (pin "32") (pinfunction "32_32") (pintype "passive+no_connect"))
    )
    (net (code "67") (name "unconnected-(X6-Pad33)") (class "Default")
      (node (ref "X6") (pin "33") (pinfunction "33_33") (pintype "passive+no_connect"))
    )
    (net (code "68") (name "unconnected-(X6-Pad35)") (class "Default")
      (node (ref "X6") (pin "35") (pinfunction "35_35") (pintype "passive+no_connect"))
    )
    (net (code "69") (name "unconnected-(X6-Pad36)") (class "Default")
      (node (ref "X6") (pin "36") (pinfunction "36_36") (pintype "passive+no_connect"))
    )
    (net (code "70") (name "unconnected-(X6-Pad37)") (class "Default")
      (node (ref "X6") (pin "37") (pinfunction "37_37") (pintype "passive+no_connect"))
    )
    (net (code "71") (name "unconnected-(X6-Pad38)") (class "Default")
      (node (ref "X6") (pin "38") (pinfunction "38_38") (pintype "passive+no_connect"))
    )
    (net (code "72") (name "unconnected-(X6-Pad40)") (class "Default")
      (node (ref "X6") (pin "40") (pinfunction "40_40") (pintype "passive+no_connect"))
    )
  )
)
